# 1.net
KiCad netlist of a schematic drawn in Altium Designer
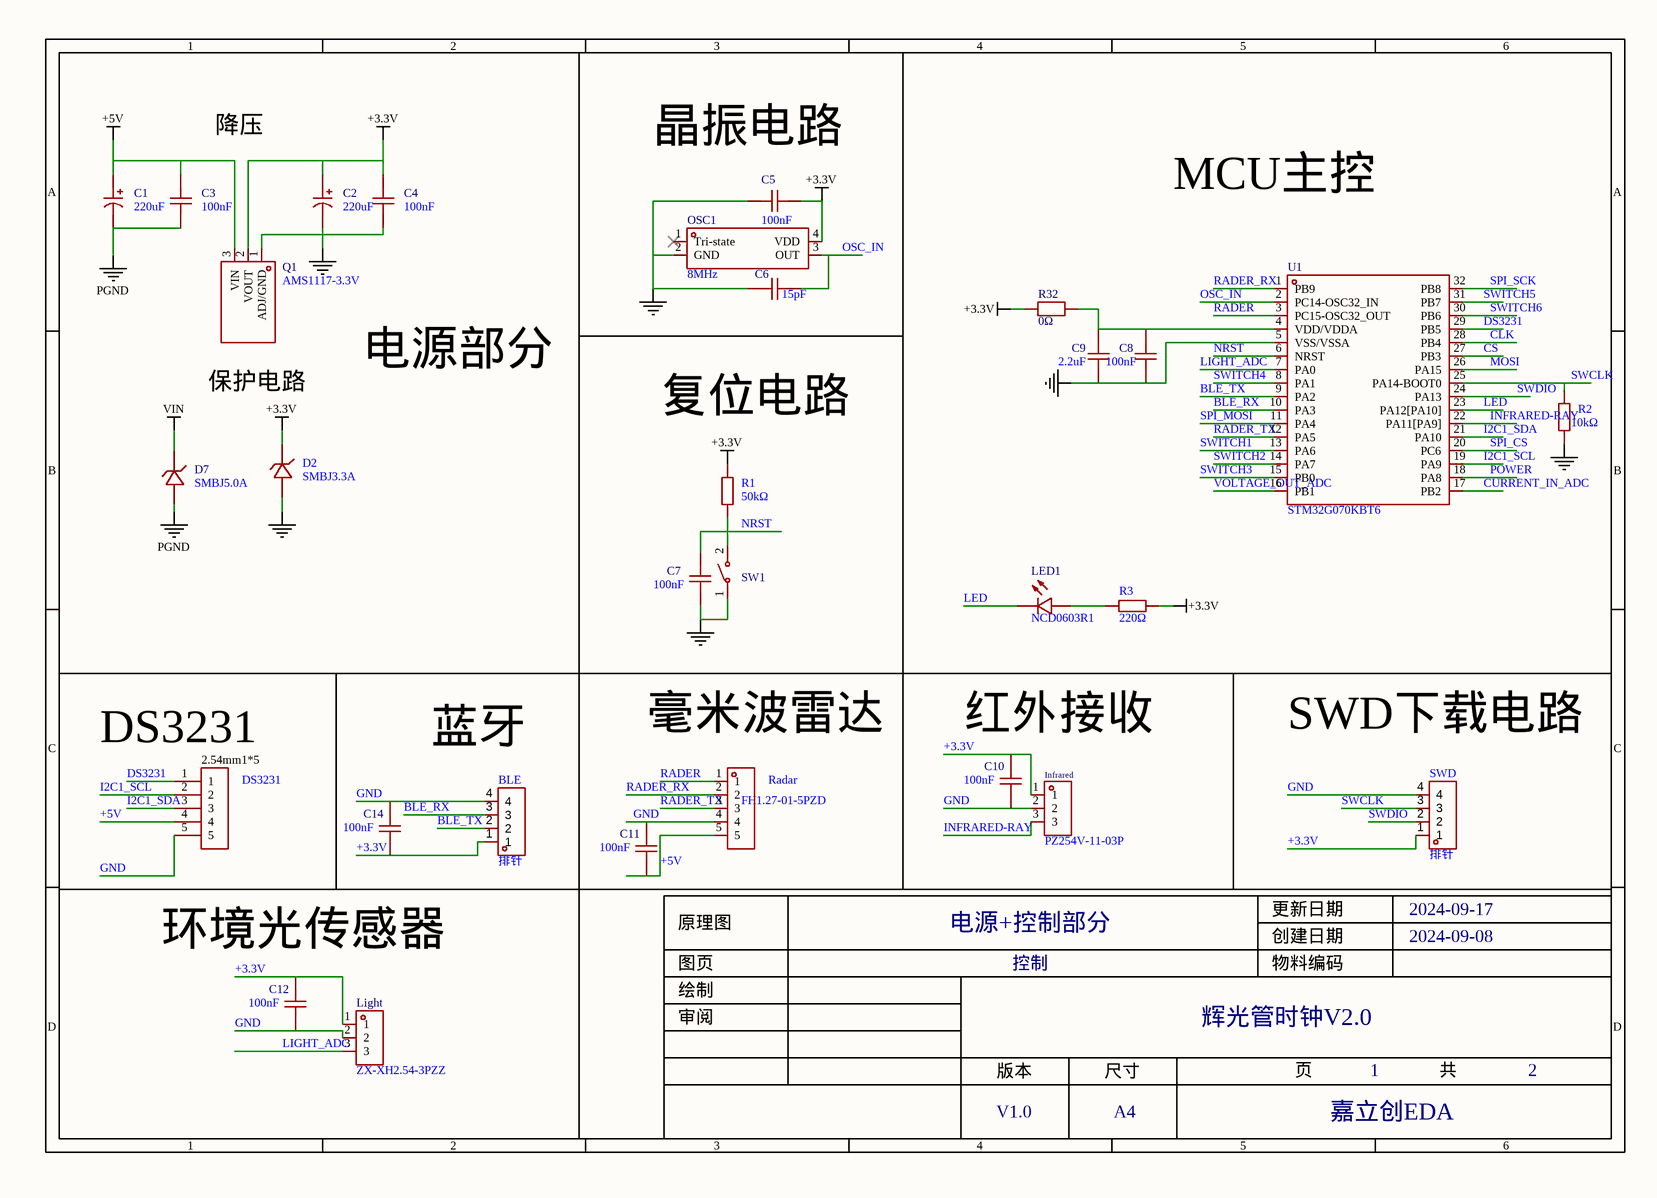
[diagram p0: 1_控制.schdoc]

(export (version "E")
  (design (tool "Eeschema 10.0.6"))
  (components
    (comp (ref "BLE")
      (value "排针")
      (footprint "SIP-2.54MM-4P-CJT-H8.54")
      (libsource (lib "altium-import") (part "root_3_排针_"))
    )
    (comp (ref "C1")
      (value "220uF")
      (footprint "CAP-SMD_BD6.3-L6.6-W6.6-FD")
      (fields
        (field (name "MANUFACTURER") "KNSCHA(科尼盛)")
        (field (name "MANUFACTURER PART") "RVT220UF10V67RV0037")
        (field (name "TOLERANCE") "±20%")
      )
      (libsource (lib "altium-import") (part "root_3_RVT220UF10V67RV0037_"))
    )
    (comp (ref "C2")
      (value "220uF")
      (footprint "CAP-SMD_BD6.3-L6.6-W6.6-FD")
      (fields
        (field (name "MANUFACTURER") "KNSCHA(科尼盛)")
        (field (name "MANUFACTURER PART") "RVT220UF10V67RV0037")
        (field (name "TOLERANCE") "±20%")
      )
      (libsource (lib "altium-import") (part "root_3_RVT220UF10V67RV0037_"))
    )
    (comp (ref "C3")
      (value "100nF")
      (footprint "C0603")
      (fields
        (field (name "MANUFACTURER") "YAGEO(国巨)")
        (field (name "MANUFACTURER PART") "CC0603KRX7R9BB104")
        (field (name "TOLERANCE") "±10%")
      )
      (libsource (lib "altium-import") (part "root_1_CC0603KRX7R9BB104_"))
    )
    (comp (ref "C4")
      (value "100nF")
      (footprint "C0603")
      (fields
        (field (name "MANUFACTURER") "YAGEO(国巨)")
        (field (name "MANUFACTURER PART") "CC0603KRX7R9BB104")
        (field (name "TOLERANCE") "±10%")
      )
      (libsource (lib "altium-import") (part "root_1_CC0603KRX7R9BB104_"))
    )
    (comp (ref "C5")
      (value "100nF")
      (footprint "C0603")
      (fields
        (field (name "MANUFACTURER") "YAGEO(国巨)")
        (field (name "MANUFACTURER PART") "CC0603KRX7R9BB104")
        (field (name "TOLERANCE") "±10%")
      )
      (libsource (lib "altium-import") (part "root_2_CC0603KRX7R9BB104_"))
    )
    (comp (ref "C6")
      (value "15pF")
      (footprint "C0603")
      (fields
        (field (name "MANUFACTURER") "YAGEO(国巨)")
        (field (name "MANUFACTURER PART") "CC0603KRX7R9BB104")
        (field (name "TOLERANCE") "±10%")
      )
      (libsource (lib "altium-import") (part "root_2_CC0603KRX7R9BB104_"))
    )
    (comp (ref "C7")
      (value "100nF")
      (footprint "C0603")
      (fields
        (field (name "MANUFACTURER") "YAGEO(国巨)")
        (field (name "MANUFACTURER PART") "CC0603KRX7R9BB104")
        (field (name "TOLERANCE") "±10%")
      )
      (libsource (lib "altium-import") (part "root_1_CC0603KRX7R9BB104_"))
    )
    (comp (ref "C8")
      (value "100nF")
      (footprint "C0603")
      (fields
        (field (name "MANUFACTURER") "YAGEO(国巨)")
        (field (name "MANUFACTURER PART") "CC0603KRX7R9BB104")
        (field (name "TOLERANCE") "±10%")
      )
      (libsource (lib "altium-import") (part "root_1_CC0603KRX7R9BB104_"))
    )
    (comp (ref "C9")
      (value "2.2uF")
      (footprint "C0603")
      (fields
        (field (name "MANUFACTURER") "YAGEO(国巨)")
        (field (name "MANUFACTURER PART") "CC0603KRX7R9BB104")
        (field (name "TOLERANCE") "±10%")
      )
      (libsource (lib "altium-import") (part "root_1_CC0603KRX7R9BB104_"))
    )
    (comp (ref "C10")
      (value "100nF")
      (footprint "C0603")
      (fields
        (field (name "MANUFACTURER") "YAGEO(国巨)")
        (field (name "MANUFACTURER PART") "CC0603KRX7R9BB104")
        (field (name "TOLERANCE") "±10%")
      )
      (libsource (lib "altium-import") (part "root_1_CC0603KRX7R9BB104_"))
    )
    (comp (ref "C11")
      (value "100nF")
      (footprint "C0603")
      (fields
        (field (name "MANUFACTURER") "YAGEO(国巨)")
        (field (name "MANUFACTURER PART") "CC0603KRX7R9BB104")
        (field (name "TOLERANCE") "±10%")
      )
      (libsource (lib "altium-import") (part "root_1_CC0603KRX7R9BB104_"))
    )
    (comp (ref "C12")
      (value "100nF")
      (footprint "C0603")
      (fields
        (field (name "MANUFACTURER") "YAGEO(国巨)")
        (field (name "MANUFACTURER PART") "CC0603KRX7R9BB104")
        (field (name "TOLERANCE") "±10%")
      )
      (libsource (lib "altium-import") (part "root_1_CC0603KRX7R9BB104_"))
    )
    (comp (ref "C14")
      (value "100nF")
      (footprint "C0603")
      (fields
        (field (name "MANUFACTURER") "YAGEO(国巨)")
        (field (name "MANUFACTURER PART") "CC0603KRX7R9BB104")
        (field (name "TOLERANCE") "±10%")
      )
      (libsource (lib "altium-import") (part "root_1_CC0603KRX7R9BB104_"))
    )
    (comp (ref "D2")
      (value "SMBJ3.3A")
      (footprint "SMB_L4.6-W3.6-LS5.3-RD")
      (fields (field (name "MANUFACTURER") "JKSEMI(金开盛)"))
      (libsource (lib "altium-import") (part "root_3_SMBJ3.3A_C362089_"))
    )
    (comp (ref "D7")
      (value "SMBJ5.0A")
      (footprint "SMB_L4.4-W3.6-LS5.3-RD")
      (fields (field (name "MANUFACTURER") "TWGMC(台湾迪嘉)"))
      (libsource (lib "altium-import") (part "root_3_SMBJ5.0A_C726811_"))
    )
    (comp (ref "DS3231")
      (value "~")
      (footprint "2.54mm1*5")
      (libsource (lib "altium-import") (part "root_0_2.54mm1*5_"))
    )
    (comp (ref "Infrared")
      (value "PZ254V-11-03P")
      (footprint "HDR-TH_3P-P2.54-V-M")
      (fields (field (name "MANUFACTURER") "XFCN(兴飞)"))
      (libsource (lib "altium-import") (part "root_0_PZ254V-11-03P_"))
    )
    (comp (ref "LED1")
      (value "NCD0603R1")
      (footprint "LED0603-RD_RED")
      (fields (field (name "MANUFACTURER") "国星光电"))
      (libsource (lib "altium-import") (part "root_0_NCD0603R1_C84263_"))
    )
    (comp (ref "Light")
      (value "ZX-XH2.54-3PZZ")
      (footprint "CONN-TH_3P-P2.54_2501S-3P")
      (fields (field (name "MANUFACTURER") "Megastar(兆星)"))
      (libsource (lib "altium-import") (part "root_0_ZX-XH2.54-3PZZ_"))
    )
    (comp (ref "OSC1")
      (value "8MHz")
      (footprint "OSC-SMD_4P-L3.2-W2.5-BL-1")
      (fields
        (field (name "MANUFACTURER") "YXC(扬兴晶振)")
        (field (name "MANUFACTURER PART") "OT2EL4C4JI-111OLP-8M")
      )
      (libsource (lib "altium-import") (part "root_0_OT2EL4C4JI-111OLP-8M_"))
    )
    (comp (ref "Q1")
      (value "AMS1117-3.3V")
      (footprint "SOT-89-3_L4.5-W2.5-P1.50-LS4.2-BR")
      (fields (field (name "MANUFACTURER") "MSKSEMI(美森科)"))
      (libsource (lib "altium-import") (part "root_3_AMS1117-3.3V_C5120796_"))
    )
    (comp (ref "R1")
      (value "50kΩ")
      (footprint "r0603")
      (fields
        (field (name "MANUFACTURER") "UNI-ROYAL(厚声)")
        (field (name "MANUFACTURER PART") "0805W8F1002T5E")
        (field (name "TOLERANCE") "±1%")
      )
      (libsource (lib "altium-import") (part "root_1_0805W8F1002T5E_C17414_"))
    )
    (comp (ref "R2")
      (value "10kΩ")
      (footprint "r0603")
      (fields
        (field (name "MANUFACTURER") "UNI-ROYAL(厚声)")
        (field (name "MANUFACTURER PART") "0805W8F1002T5E")
        (field (name "TOLERANCE") "±1%")
      )
      (libsource (lib "altium-import") (part "root_1_0805W8F1002T5E_C17414_"))
    )
    (comp (ref "R3")
      (value "220Ω")
      (footprint "r0603")
      (fields
        (field (name "MANUFACTURER") "UNI-ROYAL(厚声)")
        (field (name "MANUFACTURER PART") "0805W8F1002T5E")
        (field (name "TOLERANCE") "±1%")
      )
      (libsource (lib "altium-import") (part "root_2_0805W8F1002T5E_C17414_"))
    )
    (comp (ref "R32") (value "0Ω") (footprint "R0603") (libsource (lib "altium-import") (part "root_2_5mΩ_")))
    (comp (ref "Radar")
      (value "FH1.27-01-5PZD")
      (footprint "HDR-TH_5P-P1.27-V-M")
      (fields (field (name "MANUFACTURER") "XUNPU(讯普)"))
      (libsource (lib "altium-import") (part "root_0_FH1.27-01-5PZD_"))
    )
    (comp (ref "SW1")
      (value "TS-1088R-02026")
      (footprint "SW-SMD_L3.9-W3.0-P4.45")
      (fields (field (name "MANUFACTURER") "XUNPU(讯普)"))
      (libsource (lib "altium-import") (part "root_1_TS-1088R-02026_"))
    )
    (comp (ref "SWD")
      (value "排针")
      (footprint "SIP-2.54MM-4P-CJT-H8.54")
      (libsource (lib "altium-import") (part "root_3_排针_"))
    )
    (comp (ref "U1")
      (value "STM32G070KBT6")
      (footprint "LQFP-32_L7.0-W7.0-P0.80-LS9.0-BL")
      (fields (field (name "MANUFACTURER") "ST(意法半导体)"))
      (libsource (lib "altium-import") (part "root_0_STM32G070KBT6_"))
    )
  )
  (nets
    (net (code "1") (name "+3.3V") (class "Default")
      (node (ref "BLE") (pin "1") (pinfunction "1_1") (pintype "passive"))
      (node (ref "C10") (pin "2") (pinfunction "2_2") (pintype "passive"))
      (node (ref "C12") (pin "2") (pinfunction "2_2") (pintype "passive"))
      (node (ref "C14") (pin "1") (pinfunction "1_1") (pintype "passive"))
      (node (ref "C2") (pin "1") (pinfunction "1_1") (pintype "passive"))
      (node (ref "C4") (pin "2") (pinfunction "2_2") (pintype "passive"))
      (node (ref "C5") (pin "1") (pinfunction "1_1") (pintype "passive"))
      (node (ref "D2") (pin "1") (pinfunction "1_1") (pintype "passive"))
      (node (ref "Infrared") (pin "1") (pinfunction "1_1") (pintype "passive"))
      (node (ref "Light") (pin "1") (pinfunction "1_1") (pintype "passive"))
      (node (ref "OSC1") (pin "4") (pinfunction "VDD_4") (pintype "passive"))
      (node (ref "Q1") (pin "2") (pinfunction "VOUT_2") (pintype "passive"))
      (node (ref "R1") (pin "2") (pinfunction "2_2") (pintype "passive"))
      (node (ref "R3") (pin "1") (pinfunction "1_1") (pintype "passive"))
      (node (ref "R32") (pin "2") (pinfunction "2_2") (pintype "passive"))
      (node (ref "SWD") (pin "1") (pinfunction "1_1") (pintype "passive"))
    )
    (net (code "2") (name "+5V") (class "Default")
      (node (ref "C1") (pin "1") (pinfunction "1_1") (pintype "passive"))
      (node (ref "C11") (pin "1") (pinfunction "1_1") (pintype "passive"))
      (node (ref "C3") (pin "2") (pinfunction "2_2") (pintype "passive"))
      (node (ref "DS3231") (pin "4") (pinfunction "4_4") (pintype "passive"))
      (node (ref "Q1") (pin "3") (pinfunction "VIN_3") (pintype "passive"))
      (node (ref "Radar") (pin "5") (pinfunction "5_5") (pintype "passive"))
    )
    (net (code "3") (name "/BLE_RX") (class "Default")
      (node (ref "BLE") (pin "3") (pinfunction "3_3") (pintype "passive"))
      (node (ref "U1") (pin "10") (pinfunction "PA3_10") (pintype "passive"))
    )
    (net (code "4") (name "/BLE_TX") (class "Default")
      (node (ref "BLE") (pin "2") (pinfunction "2_2") (pintype "passive"))
      (node (ref "U1") (pin "9") (pinfunction "PA2_9") (pintype "passive"))
    )
    (net (code "5") (name "/CLK") (class "Default")
      (node (ref "U1") (pin "28") (pinfunction "PB4_28") (pintype "passive"))
    )
    (net (code "6") (name "/CS") (class "Default")
      (node (ref "U1") (pin "27") (pinfunction "PB3_27") (pintype "passive"))
    )
    (net (code "7") (name "/CURRENT_IN_ADC") (class "Default")
      (node (ref "U1") (pin "17") (pinfunction "PB2_17") (pintype "passive"))
    )
    (net (code "8") (name "/DS3231") (class "Default")
      (node (ref "DS3231") (pin "1") (pinfunction "1_1") (pintype "passive"))
      (node (ref "U1") (pin "29") (pinfunction "PB5_29") (pintype "passive"))
    )
    (net (code "9") (name "/I2C1_SCL") (class "Default")
      (node (ref "DS3231") (pin "2") (pinfunction "2_2") (pintype "passive"))
      (node (ref "U1") (pin "19") (pinfunction "PA9_19") (pintype "passive"))
    )
    (net (code "10") (name "/I2C1_SDA") (class "Default")
      (node (ref "DS3231") (pin "3") (pinfunction "3_3") (pintype "passive"))
      (node (ref "U1") (pin "21") (pinfunction "PA10_21") (pintype "passive"))
    )
    (net (code "11") (name "/INFRARED-RAY") (class "Default")
      (node (ref "Infrared") (pin "3") (pinfunction "3_3") (pintype "passive"))
      (node (ref "U1") (pin "22") (pinfunction "PA11[PA9]_22") (pintype "passive"))
    )
    (net (code "12") (name "/LED") (class "Default")
      (node (ref "LED1") (pin "1") (pinfunction "K_1") (pintype "passive"))
      (node (ref "U1") (pin "23") (pinfunction "PA12[PA10]_23") (pintype "passive"))
    )
    (net (code "13") (name "/LIGHT_ADC") (class "Default")
      (node (ref "Light") (pin "3") (pinfunction "3_3") (pintype "passive"))
      (node (ref "U1") (pin "7") (pinfunction "PA0_7") (pintype "passive"))
    )
    (net (code "14") (name "/MOSI") (class "Default")
      (node (ref "U1") (pin "26") (pinfunction "PA15_26") (pintype "passive"))
    )
    (net (code "15") (name "/NRST") (class "Default")
      (node (ref "C7") (pin "2") (pinfunction "2_2") (pintype "passive"))
      (node (ref "R1") (pin "1") (pinfunction "1_1") (pintype "passive"))
      (node (ref "SW1") (pin "2") (pinfunction "2_2") (pintype "passive"))
      (node (ref "U1") (pin "6") (pinfunction "NRST_6") (pintype "passive"))
    )
    (net (code "16") (name "/OSC_IN") (class "Default")
      (node (ref "C6") (pin "1") (pinfunction "1_1") (pintype "passive"))
      (node (ref "OSC1") (pin "3") (pinfunction "OUT_3") (pintype "passive"))
      (node (ref "U1") (pin "2") (pinfunction "PC14-OSC32_IN_2") (pintype "passive"))
    )
    (net (code "17") (name "/POWER") (class "Default")
      (node (ref "U1") (pin "18") (pinfunction "PA8_18") (pintype "passive"))
    )
    (net (code "18") (name "/RADER") (class "Default")
      (node (ref "Radar") (pin "1") (pinfunction "1_1") (pintype "passive"))
      (node (ref "U1") (pin "3") (pinfunction "PC15-OSC32_OUT_3") (pintype "passive"))
    )
    (net (code "19") (name "/RADER_RX") (class "Default")
      (node (ref "Radar") (pin "2") (pinfunction "2_2") (pintype "passive"))
      (node (ref "U1") (pin "1") (pinfunction "PB9_1") (pintype "passive"))
    )
    (net (code "20") (name "/RADER_TX") (class "Default")
      (node (ref "Radar") (pin "3") (pinfunction "3_3") (pintype "passive"))
      (node (ref "U1") (pin "12") (pinfunction "PA5_12") (pintype "passive"))
    )
    (net (code "21") (name "/SPI_CS") (class "Default")
      (node (ref "U1") (pin "20") (pinfunction "PC6_20") (pintype "passive"))
    )
    (net (code "22") (name "/SPI_MOSI") (class "Default")
      (node (ref "U1") (pin "11") (pinfunction "PA4_11") (pintype "passive"))
    )
    (net (code "23") (name "/SPI_SCK") (class "Default")
      (node (ref "U1") (pin "32") (pinfunction "PB8_32") (pintype "passive"))
    )
    (net (code "24") (name "/SWCLK") (class "Default")
      (node (ref "R2") (pin "2") (pinfunction "2_2") (pintype "passive"))
      (node (ref "SWD") (pin "3") (pinfunction "3_3") (pintype "passive"))
      (node (ref "U1") (pin "25") (pinfunction "PA14-BOOT0_25") (pintype "passive"))
    )
    (net (code "25") (name "/SWDIO") (class "Default")
      (node (ref "SWD") (pin "2") (pinfunction "2_2") (pintype "passive"))
      (node (ref "U1") (pin "24") (pinfunction "PA13_24") (pintype "passive"))
    )
    (net (code "26") (name "/SWITCH1") (class "Default")
      (node (ref "U1") (pin "13") (pinfunction "PA6_13") (pintype "passive"))
    )
    (net (code "27") (name "/SWITCH2") (class "Default")
      (node (ref "U1") (pin "14") (pinfunction "PA7_14") (pintype "passive"))
    )
    (net (code "28") (name "/SWITCH3") (class "Default")
      (node (ref "U1") (pin "15") (pinfunction "PB0_15") (pintype "passive"))
    )
    (net (code "29") (name "/SWITCH4") (class "Default")
      (node (ref "U1") (pin "8") (pinfunction "PA1_8") (pintype "passive"))
    )
    (net (code "30") (name "/SWITCH5") (class "Default")
      (node (ref "U1") (pin "31") (pinfunction "PB7_31") (pintype "passive"))
    )
    (net (code "31") (name "/SWITCH6") (class "Default")
      (node (ref "U1") (pin "30") (pinfunction "PB6_30") (pintype "passive"))
    )
    (net (code "32") (name "/VOLTAGE_OUT_ADC") (class "Default")
      (node (ref "U1") (pin "16") (pinfunction "PB1_16") (pintype "passive"))
    )
    (net (code "33") (name "GND") (class "Default")
      (node (ref "BLE") (pin "4") (pinfunction "4_4") (pintype "passive"))
      (node (ref "C10") (pin "1") (pinfunction "1_1") (pintype "passive"))
      (node (ref "C11") (pin "2") (pinfunction "2_2") (pintype "passive"))
      (node (ref "C12") (pin "1") (pinfunction "1_1") (pintype "passive"))
      (node (ref "C14") (pin "2") (pinfunction "2_2") (pintype "passive"))
      (node (ref "C2") (pin "2") (pinfunction "2_2") (pintype "passive"))
      (node (ref "C4") (pin "1") (pinfunction "1_1") (pintype "passive"))
      (node (ref "C5") (pin "2") (pinfunction "2_2") (pintype "passive"))
      (node (ref "C6") (pin "2") (pinfunction "2_2") (pintype "passive"))
      (node (ref "C7") (pin "1") (pinfunction "1_1") (pintype "passive"))
      (node (ref "C8") (pin "1") (pinfunction "1_1") (pintype "passive"))
      (node (ref "C9") (pin "1") (pinfunction "1_1") (pintype "passive"))
      (node (ref "D2") (pin "2") (pinfunction "2_2") (pintype "passive"))
      (node (ref "DS3231") (pin "5") (pinfunction "5_5") (pintype "passive"))
      (node (ref "Infrared") (pin "2") (pinfunction "2_2") (pintype "passive"))
      (node (ref "Light") (pin "2") (pinfunction "2_2") (pintype "passive"))
      (node (ref "OSC1") (pin "2") (pinfunction "GND_2") (pintype "passive"))
      (node (ref "Q1") (pin "1") (pinfunction "ADJ/GND_1") (pintype "passive"))
      (node (ref "R2") (pin "1") (pinfunction "1_1") (pintype "passive"))
      (node (ref "Radar") (pin "4") (pinfunction "4_4") (pintype "passive"))
      (node (ref "SW1") (pin "1") (pinfunction "1_1") (pintype "passive"))
      (node (ref "SWD") (pin "4") (pinfunction "4_4") (pintype "passive"))
      (node (ref "U1") (pin "5") (pinfunction "VSS/VSSA_5") (pintype "passive"))
    )
    (net (code "34") (name "Net-(LED1-A)") (class "Default")
      (node (ref "LED1") (pin "2") (pinfunction "A_2") (pintype "passive"))
      (node (ref "R3") (pin "2") (pinfunction "2_2") (pintype "passive"))
    )
    (net (code "35") (name "Net-(U1-VDD{slash}VDDA)") (class "Default")
      (node (ref "C8") (pin "2") (pinfunction "2_2") (pintype "passive"))
      (node (ref "C9") (pin "2") (pinfunction "2_2") (pintype "passive"))
      (node (ref "R32") (pin "1") (pinfunction "1_1") (pintype "passive"))
      (node (ref "U1") (pin "4") (pinfunction "VDD/VDDA_4") (pintype "passive"))
    )
    (net (code "36") (name "PGND") (class "Default")
      (node (ref "C1") (pin "2") (pinfunction "2_2") (pintype "passive"))
      (node (ref "C3") (pin "1") (pinfunction "1_1") (pintype "passive"))
      (node (ref "D7") (pin "2") (pinfunction "A_2") (pintype "passive"))
    )
    (net (code "37") (name "VIN") (class "Default")
      (node (ref "D7") (pin "1") (pinfunction "C_1") (pintype "passive"))
    )
    (net (code "38") (name "unconnected-(OSC1-Tri-state-Pad1)") (class "Default")
      (node (ref "OSC1") (pin "1") (pinfunction "Tri-state_1") (pintype "passive+no_connect"))
    )
  )
)
